# board.net
KiCad netlist of a schematic drawn in EAGLE
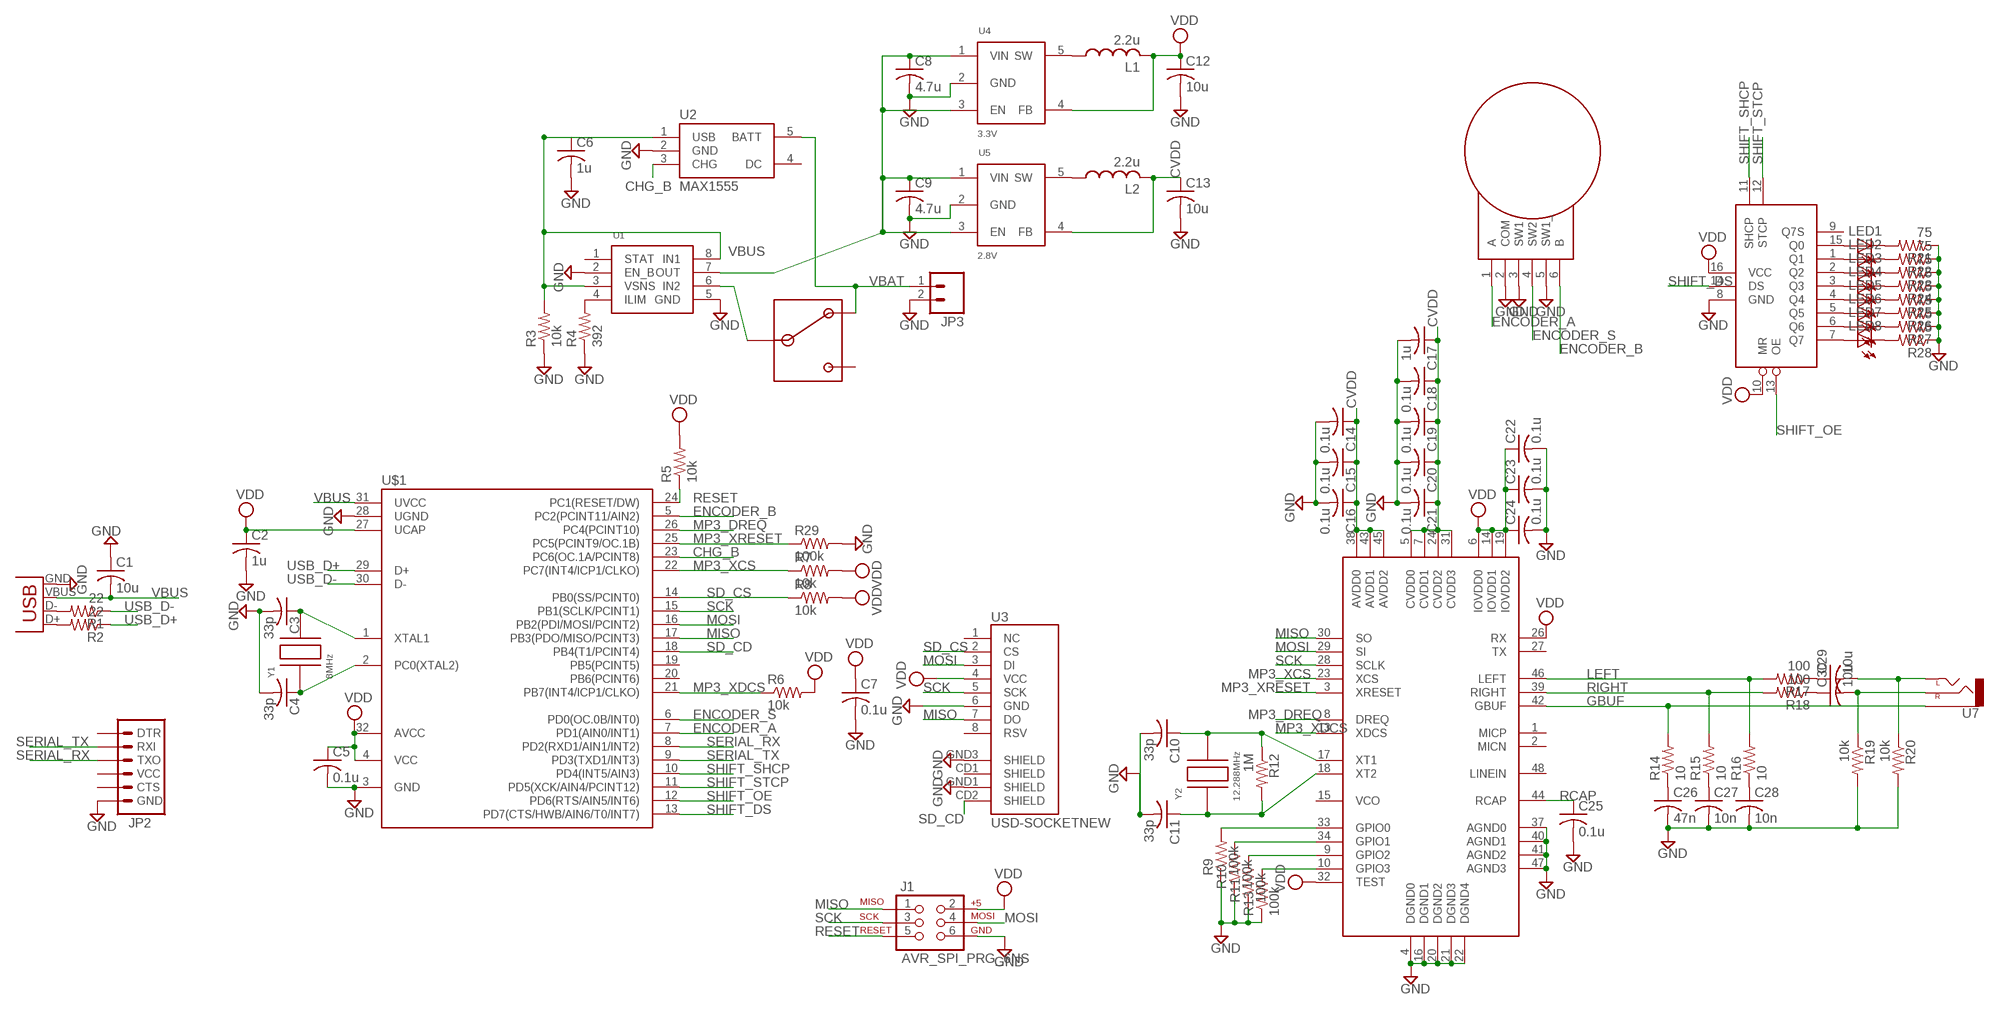
[diagram p0: schematic, sheet 1]

(export (version "E")
  (design (tool "Eeschema 10.0.6"))
  (components
    (comp (ref "C1")
      (value "10u")
      (footprint "eagle-import:C0603K")
      (libsource (lib "eagle-import") (part "C-USC0603K"))
    )
    (comp (ref "C2")
      (value "1u")
      (footprint "eagle-import:C0603K")
      (libsource (lib "eagle-import") (part "C-USC0603K"))
    )
    (comp (ref "C3")
      (value "33p")
      (footprint "eagle-import:C0603K")
      (libsource (lib "eagle-import") (part "C-USC0603K"))
    )
    (comp (ref "C4")
      (value "33p")
      (footprint "eagle-import:C0603K")
      (libsource (lib "eagle-import") (part "C-USC0603K"))
    )
    (comp (ref "C5")
      (value "0.1u")
      (footprint "eagle-import:C0603K")
      (libsource (lib "eagle-import") (part "C-USC0603K"))
    )
    (comp (ref "C6")
      (value "1u")
      (footprint "eagle-import:C0603K")
      (libsource (lib "eagle-import") (part "C-USC0603K"))
    )
    (comp (ref "C7")
      (value "0.1u")
      (footprint "eagle-import:C0603K")
      (libsource (lib "eagle-import") (part "C-USC0603K"))
    )
    (comp (ref "C8")
      (value "4.7u")
      (footprint "eagle-import:C0603K")
      (libsource (lib "eagle-import") (part "C-USC0603K"))
    )
    (comp (ref "C9")
      (value "4.7u")
      (footprint "eagle-import:C0603K")
      (libsource (lib "eagle-import") (part "C-USC0603K"))
    )
    (comp (ref "C10")
      (value "33p")
      (footprint "eagle-import:C0603K")
      (libsource (lib "eagle-import") (part "C-USC0603K"))
    )
    (comp (ref "C11")
      (value "33p")
      (footprint "eagle-import:C0603K")
      (libsource (lib "eagle-import") (part "C-USC0603K"))
    )
    (comp (ref "C12")
      (value "10u")
      (footprint "eagle-import:C0603K")
      (libsource (lib "eagle-import") (part "C-USC0603K"))
    )
    (comp (ref "C13")
      (value "10u")
      (footprint "eagle-import:C0603K")
      (libsource (lib "eagle-import") (part "C-USC0603K"))
    )
    (comp (ref "C14")
      (value "0.1u")
      (footprint "eagle-import:C0603K")
      (libsource (lib "eagle-import") (part "C-USC0603K"))
    )
    (comp (ref "C15")
      (value "0.1u")
      (footprint "eagle-import:C0603K")
      (libsource (lib "eagle-import") (part "C-USC0603K"))
    )
    (comp (ref "C16")
      (value "0.1u")
      (footprint "eagle-import:C0603K")
      (libsource (lib "eagle-import") (part "C-USC0603K"))
    )
    (comp (ref "C17")
      (value "1u")
      (footprint "eagle-import:C0603K")
      (libsource (lib "eagle-import") (part "C-USC0603K"))
    )
    (comp (ref "C18")
      (value "0.1u")
      (footprint "eagle-import:C0603K")
      (libsource (lib "eagle-import") (part "C-USC0603K"))
    )
    (comp (ref "C19")
      (value "0.1u")
      (footprint "eagle-import:C0603K")
      (libsource (lib "eagle-import") (part "C-USC0603K"))
    )
    (comp (ref "C20")
      (value "0.1u")
      (footprint "eagle-import:C0603K")
      (libsource (lib "eagle-import") (part "C-USC0603K"))
    )
    (comp (ref "C21")
      (value "0.1u")
      (footprint "eagle-import:C0603K")
      (libsource (lib "eagle-import") (part "C-USC0603K"))
    )
    (comp (ref "C22")
      (value "0.1u")
      (footprint "eagle-import:C0603K")
      (libsource (lib "eagle-import") (part "C-USC0603K"))
    )
    (comp (ref "C23")
      (value "0.1u")
      (footprint "eagle-import:C0603K")
      (libsource (lib "eagle-import") (part "C-USC0603K"))
    )
    (comp (ref "C24")
      (value "0.1u")
      (footprint "eagle-import:C0603K")
      (libsource (lib "eagle-import") (part "C-USC0603K"))
    )
    (comp (ref "C25")
      (value "0.1u")
      (footprint "eagle-import:C0603K")
      (libsource (lib "eagle-import") (part "C-USC0603K"))
    )
    (comp (ref "C26")
      (value "47n")
      (footprint "eagle-import:C0603K")
      (libsource (lib "eagle-import") (part "C-USC0603K"))
    )
    (comp (ref "C27")
      (value "10n")
      (footprint "eagle-import:C0603K")
      (libsource (lib "eagle-import") (part "C-USC0603K"))
    )
    (comp (ref "C28")
      (value "10n")
      (footprint "eagle-import:C0603K")
      (libsource (lib "eagle-import") (part "C-USC0603K"))
    )
    (comp (ref "C29")
      (value "10u")
      (footprint "eagle-import:C0603K")
      (libsource (lib "eagle-import") (part "C-USC0603K"))
    )
    (comp (ref "C30")
      (value "10u")
      (footprint "eagle-import:C0603K")
      (libsource (lib "eagle-import") (part "C-USC0603K"))
    )
    (comp (ref "J1")
      (value "AVR_SPI_PRG_6NS")
      (footprint "eagle-import:2X3-NS")
      (libsource (lib "eagle-import") (part "AVR_SPI_PRG_6NS"))
    )
    (comp (ref "JP1")
      (value "USBSMD")
      (footprint "eagle-import:USB-MINIB")
      (libsource (lib "eagle-import") (part "USBSMD"))
    )
    (comp (ref "JP2")
      (value "ARDUINO_SERIAL_PROGRAMLOCK")
      (footprint "eagle-import:1X06_LOCK")
      (libsource (lib "eagle-import") (part "ARDUINO_SERIAL_PROGRAMLOCK"))
    )
    (comp (ref "JP3")
      (value "M02PTH")
      (footprint "eagle-import:1X02")
      (libsource (lib "eagle-import") (part "M02PTH"))
    )
    (comp (ref "L1")
      (value "2.2u")
      (footprint "eagle-import:IHLP-2020CZ-11")
      (libsource (lib "eagle-import") (part "IHLP-2020CZ-11"))
    )
    (comp (ref "L2")
      (value "2.2u")
      (footprint "eagle-import:IHLP-2020CZ-11")
      (libsource (lib "eagle-import") (part "IHLP-2020CZ-11"))
    )
    (comp (ref "LED1")
      (value "LED1206")
      (footprint "eagle-import:LED-1206")
      (libsource (lib "eagle-import") (part "LED1206"))
    )
    (comp (ref "LED2")
      (value "LED1206")
      (footprint "eagle-import:LED-1206")
      (libsource (lib "eagle-import") (part "LED1206"))
    )
    (comp (ref "LED3")
      (value "LED1206")
      (footprint "eagle-import:LED-1206")
      (libsource (lib "eagle-import") (part "LED1206"))
    )
    (comp (ref "LED4")
      (value "LED1206")
      (footprint "eagle-import:LED-1206")
      (libsource (lib "eagle-import") (part "LED1206"))
    )
    (comp (ref "LED5")
      (value "LED1206")
      (footprint "eagle-import:LED-1206")
      (libsource (lib "eagle-import") (part "LED1206"))
    )
    (comp (ref "LED6")
      (value "LED1206")
      (footprint "eagle-import:LED-1206")
      (libsource (lib "eagle-import") (part "LED1206"))
    )
    (comp (ref "LED7")
      (value "LED1206")
      (footprint "eagle-import:LED-1206")
      (libsource (lib "eagle-import") (part "LED1206"))
    )
    (comp (ref "LED8")
      (value "LED1206")
      (footprint "eagle-import:LED-1206")
      (libsource (lib "eagle-import") (part "LED1206"))
    )
    (comp (ref "R1")
      (value "22")
      (footprint "eagle-import:R0603W")
      (libsource (lib "eagle-import") (part "R-US_R0603W"))
    )
    (comp (ref "R2")
      (value "22")
      (footprint "eagle-import:R0603W")
      (libsource (lib "eagle-import") (part "R-US_R0603W"))
    )
    (comp (ref "R3")
      (value "10k")
      (footprint "eagle-import:R0603")
      (libsource (lib "eagle-import") (part "R-US_R0603"))
    )
    (comp (ref "R4")
      (value "392")
      (footprint "eagle-import:R0603")
      (libsource (lib "eagle-import") (part "R-US_R0603"))
    )
    (comp (ref "R5")
      (value "10k")
      (footprint "eagle-import:R0603")
      (libsource (lib "eagle-import") (part "R-US_R0603"))
    )
    (comp (ref "R6")
      (value "10k")
      (footprint "eagle-import:R0603W")
      (libsource (lib "eagle-import") (part "R-US_R0603W"))
    )
    (comp (ref "R7")
      (value "10k")
      (footprint "eagle-import:R0603W")
      (libsource (lib "eagle-import") (part "R-US_R0603W"))
    )
    (comp (ref "R8")
      (value "10k")
      (footprint "eagle-import:R0603W")
      (libsource (lib "eagle-import") (part "R-US_R0603W"))
    )
    (comp (ref "R9")
      (value "100k")
      (footprint "eagle-import:R0603W")
      (libsource (lib "eagle-import") (part "R-US_R0603W"))
    )
    (comp (ref "R10")
      (value "100k")
      (footprint "eagle-import:R0603W")
      (libsource (lib "eagle-import") (part "R-US_R0603W"))
    )
    (comp (ref "R11")
      (value "100k")
      (footprint "eagle-import:R0603W")
      (libsource (lib "eagle-import") (part "R-US_R0603W"))
    )
    (comp (ref "R12")
      (value "1M")
      (footprint "eagle-import:R0603")
      (libsource (lib "eagle-import") (part "R-US_R0603"))
    )
    (comp (ref "R13")
      (value "100k")
      (footprint "eagle-import:R0603W")
      (libsource (lib "eagle-import") (part "R-US_R0603W"))
    )
    (comp (ref "R14")
      (value "10")
      (footprint "eagle-import:R0603W")
      (libsource (lib "eagle-import") (part "R-US_R0603W"))
    )
    (comp (ref "R15")
      (value "10")
      (footprint "eagle-import:R0603W")
      (libsource (lib "eagle-import") (part "R-US_R0603W"))
    )
    (comp (ref "R16")
      (value "10")
      (footprint "eagle-import:R0603W")
      (libsource (lib "eagle-import") (part "R-US_R0603W"))
    )
    (comp (ref "R17")
      (value "100")
      (footprint "eagle-import:R0603W")
      (libsource (lib "eagle-import") (part "R-US_R0603W"))
    )
    (comp (ref "R18")
      (value "100")
      (footprint "eagle-import:R0603W")
      (libsource (lib "eagle-import") (part "R-US_R0603W"))
    )
    (comp (ref "R19")
      (value "10k")
      (footprint "eagle-import:R0603W")
      (libsource (lib "eagle-import") (part "R-US_R0603W"))
    )
    (comp (ref "R20")
      (value "10k")
      (footprint "eagle-import:R0603W")
      (libsource (lib "eagle-import") (part "R-US_R0603W"))
    )
    (comp (ref "R21")
      (value "75")
      (footprint "eagle-import:R0603W")
      (libsource (lib "eagle-import") (part "R-US_R0603W"))
    )
    (comp (ref "R22")
      (value "75")
      (footprint "eagle-import:R0603W")
      (libsource (lib "eagle-import") (part "R-US_R0603W"))
    )
    (comp (ref "R23")
      (value "75")
      (footprint "eagle-import:R0603W")
      (libsource (lib "eagle-import") (part "R-US_R0603W"))
    )
    (comp (ref "R24")
      (value "75")
      (footprint "eagle-import:R0603W")
      (libsource (lib "eagle-import") (part "R-US_R0603W"))
    )
    (comp (ref "R25")
      (value "75")
      (footprint "eagle-import:R0603W")
      (libsource (lib "eagle-import") (part "R-US_R0603W"))
    )
    (comp (ref "R26")
      (value "75")
      (footprint "eagle-import:R0603W")
      (libsource (lib "eagle-import") (part "R-US_R0603W"))
    )
    (comp (ref "R27")
      (value "75")
      (footprint "eagle-import:R0603W")
      (libsource (lib "eagle-import") (part "R-US_R0603W"))
    )
    (comp (ref "R28")
      (value "75")
      (footprint "eagle-import:R0603W")
      (libsource (lib "eagle-import") (part "R-US_R0603W"))
    )
    (comp (ref "R29")
      (value "100k")
      (footprint "eagle-import:R0603W")
      (libsource (lib "eagle-import") (part "R-US_R0603W"))
    )
    (comp (ref "S1")
      (value "JS102011SAQN")
      (footprint "eagle-import:JS102011SAQN")
      (libsource (lib "eagle-import") (part "JS102011SAQN"))
    )
    (comp (ref "S2")
      (value "EVQ-WKA")
      (footprint "eagle-import:EVQ-WKA")
      (libsource (lib "eagle-import") (part "EVQ-WKA"))
    )
    (comp (ref "U$1")
      (value "ATMEGA32U2")
      (footprint "eagle-import:TQFP32-08")
      (libsource (lib "eagle-import") (part "ATMEGA32U2"))
    )
    (comp (ref "U$2")
      (value "VS1003")
      (footprint "eagle-import:LQFP-48")
      (libsource (lib "eagle-import") (part "VS1003"))
    )
    (comp (ref "U1")
      (value "TPS2112A")
      (footprint "eagle-import:TSSOP8")
      (libsource (lib "eagle-import") (part "TPS2112A"))
    )
    (comp (ref "U2")
      (value "MAX1555")
      (footprint "eagle-import:SOT23-5")
      (libsource (lib "eagle-import") (part "MAX1555"))
    )
    (comp (ref "U3")
      (value "USD-SOCKETNEW")
      (footprint "eagle-import:MICRO-SD-SOCKET-PP")
      (libsource (lib "eagle-import") (part "USD-SOCKETNEW"))
    )
    (comp (ref "U4")
      (value "3.3V")
      (footprint "eagle-import:SOT23-5")
      (libsource (lib "eagle-import") (part "LM3671"))
    )
    (comp (ref "U5")
      (value "2.8V")
      (footprint "eagle-import:SOT23-5")
      (libsource (lib "eagle-import") (part "LM3671"))
    )
    (comp (ref "U6")
      (value "74HC595")
      (footprint "eagle-import:TSSOP16")
      (libsource (lib "eagle-import") (part "74HC595"))
    )
    (comp (ref "U7")
      (value "AUDIO-JACKSMD2")
      (footprint "eagle-import:AUDIO-JACK-3.5MM-SMD")
      (libsource (lib "eagle-import") (part "AUDIO-JACKSMD2"))
    )
    (comp (ref "Y1")
      (value "8MHz")
      (footprint "eagle-import:HC49_US")
      (libsource (lib "eagle-import") (part "CSM-7X"))
    )
    (comp (ref "Y2")
      (value "12.288MHz")
      (footprint "eagle-import:CSM-3X")
      (libsource (lib "eagle-import") (part "CSM-3X"))
    )
  )
  (nets
    (net (code "1") (name "/CHG_B") (class "Default")
      (node (ref "U$1") (pin "23") (pinfunction "PC6(OC.1A/PCINT8)_23") (pintype "bidirectional"))
      (node (ref "U2") (pin "3") (pinfunction "CHG_3") (pintype "bidirectional"))
    )
    (net (code "2") (name "/CVDD") (class "Default")
      (node (ref "C13") (pin "1") (pinfunction "1_1") (pintype "passive"))
      (node (ref "C14") (pin "1") (pinfunction "1_1") (pintype "passive"))
      (node (ref "C15") (pin "1") (pinfunction "1_1") (pintype "passive"))
      (node (ref "C16") (pin "1") (pinfunction "1_1") (pintype "passive"))
      (node (ref "C17") (pin "1") (pinfunction "1_1") (pintype "passive"))
      (node (ref "C18") (pin "1") (pinfunction "1_1") (pintype "passive"))
      (node (ref "C19") (pin "1") (pinfunction "1_1") (pintype "passive"))
      (node (ref "C20") (pin "1") (pinfunction "1_1") (pintype "passive"))
      (node (ref "C21") (pin "1") (pinfunction "1_1") (pintype "passive"))
      (node (ref "L2") (pin "P$2") (pinfunction "2_P$2") (pintype "passive"))
      (node (ref "U$2") (pin "24") (pinfunction "CVDD2_24") (pintype "bidirectional"))
      (node (ref "U$2") (pin "31") (pinfunction "CVDD3_31") (pintype "bidirectional"))
      (node (ref "U$2") (pin "38") (pinfunction "AVDD0_38") (pintype "bidirectional"))
      (node (ref "U$2") (pin "43") (pinfunction "AVDD1_43") (pintype "bidirectional"))
      (node (ref "U$2") (pin "45") (pinfunction "AVDD2_45") (pintype "bidirectional"))
      (node (ref "U$2") (pin "5") (pinfunction "CVDD0_5") (pintype "bidirectional"))
      (node (ref "U$2") (pin "7") (pinfunction "CVDD1_7") (pintype "bidirectional"))
      (node (ref "U5") (pin "4") (pinfunction "FB_4") (pintype "bidirectional"))
    )
    (net (code "3") (name "/ENCODER_A") (class "Default")
      (node (ref "S2") (pin "1") (pinfunction "A_1") (pintype "bidirectional"))
      (node (ref "U$1") (pin "7") (pinfunction "PD1(AIN0/INT1)_7") (pintype "bidirectional"))
    )
    (net (code "4") (name "/ENCODER_B") (class "Default")
      (node (ref "S2") (pin "6") (pinfunction "B_6") (pintype "bidirectional"))
      (node (ref "U$1") (pin "5") (pinfunction "PC2(PCINT11/AIN2)_5") (pintype "bidirectional"))
    )
    (net (code "5") (name "/ENCODER_S") (class "Default")
      (node (ref "S2") (pin "4") (pinfunction "SW2_4") (pintype "bidirectional"))
      (node (ref "U$1") (pin "6") (pinfunction "PD0(OC.0B/INT0)_6") (pintype "bidirectional"))
    )
    (net (code "6") (name "/GBUF") (class "Default")
      (node (ref "R14") (pin "2") (pinfunction "2_2") (pintype "passive"))
      (node (ref "U$2") (pin "42") (pinfunction "GBUF_42") (pintype "bidirectional"))
      (node (ref "U7") (pin "SLEEVE") (pinfunction "SLEEVE_SLEEVE") (pintype "bidirectional"))
    )
    (net (code "7") (name "/LEFT") (class "Default")
      (node (ref "R16") (pin "2") (pinfunction "2_2") (pintype "passive"))
      (node (ref "R17") (pin "2") (pinfunction "2_2") (pintype "passive"))
      (node (ref "U$2") (pin "46") (pinfunction "LEFT_46") (pintype "bidirectional"))
    )
    (net (code "8") (name "/MISO") (class "Default")
      (node (ref "J1") (pin "1") (pinfunction "1_1") (pintype "passive"))
      (node (ref "U$1") (pin "17") (pinfunction "PB3(PDO/MISO/PCINT3)_17") (pintype "bidirectional"))
      (node (ref "U$2") (pin "30") (pinfunction "SO_30") (pintype "bidirectional"))
      (node (ref "U3") (pin "7") (pinfunction "DO_7") (pintype "bidirectional"))
    )
    (net (code "9") (name "/MOSI") (class "Default")
      (node (ref "J1") (pin "4") (pinfunction "4_4") (pintype "passive"))
      (node (ref "U$1") (pin "16") (pinfunction "PB2(PDI/MOSI/PCINT2)_16") (pintype "bidirectional"))
      (node (ref "U$2") (pin "29") (pinfunction "SI_29") (pintype "bidirectional"))
      (node (ref "U3") (pin "3") (pinfunction "DI_3") (pintype "bidirectional"))
    )
    (net (code "10") (name "/MP3_DREQ") (class "Default")
      (node (ref "U$1") (pin "26") (pinfunction "PC4(PCINT10)_26") (pintype "bidirectional"))
      (node (ref "U$2") (pin "8") (pinfunction "DREQ_8") (pintype "bidirectional"))
    )
    (net (code "11") (name "/MP3_XCS") (class "Default")
      (node (ref "R7") (pin "1") (pinfunction "1_1") (pintype "passive"))
      (node (ref "U$1") (pin "22") (pinfunction "PC7(INT4/ICP1/CLKO)_22") (pintype "bidirectional"))
      (node (ref "U$2") (pin "23") (pinfunction "XCS_23") (pintype "bidirectional"))
    )
    (net (code "12") (name "/MP3_XDCS") (class "Default")
      (node (ref "R6") (pin "1") (pinfunction "1_1") (pintype "passive"))
      (node (ref "U$1") (pin "21") (pinfunction "PB7(INT4/ICP1/CLKO)_21") (pintype "bidirectional"))
      (node (ref "U$2") (pin "13") (pinfunction "XDCS_13") (pintype "bidirectional"))
    )
    (net (code "13") (name "/MP3_XRESET") (class "Default")
      (node (ref "R29") (pin "1") (pinfunction "1_1") (pintype "passive"))
      (node (ref "U$1") (pin "25") (pinfunction "PC5(PCINT9/OC.1B)_25") (pintype "bidirectional"))
      (node (ref "U$2") (pin "3") (pinfunction "XRESET_3") (pintype "bidirectional"))
    )
    (net (code "14") (name "/RCAP") (class "Default")
      (node (ref "C25") (pin "1") (pinfunction "1_1") (pintype "passive"))
      (node (ref "U$2") (pin "44") (pinfunction "RCAP_44") (pintype "bidirectional"))
    )
    (net (code "15") (name "/RESET") (class "Default")
      (node (ref "J1") (pin "5") (pinfunction "5_5") (pintype "passive"))
      (node (ref "R5") (pin "1") (pinfunction "1_1") (pintype "passive"))
      (node (ref "U$1") (pin "24") (pinfunction "PC1(RESET/DW)_24") (pintype "bidirectional"))
    )
    (net (code "16") (name "/RIGHT") (class "Default")
      (node (ref "R15") (pin "2") (pinfunction "2_2") (pintype "passive"))
      (node (ref "R18") (pin "2") (pinfunction "2_2") (pintype "passive"))
      (node (ref "U$2") (pin "39") (pinfunction "RIGHT_39") (pintype "bidirectional"))
    )
    (net (code "17") (name "/SCK") (class "Default")
      (node (ref "J1") (pin "3") (pinfunction "3_3") (pintype "passive"))
      (node (ref "U$1") (pin "15") (pinfunction "PB1(SCLK/PCINT1)_15") (pintype "bidirectional"))
      (node (ref "U$2") (pin "28") (pinfunction "SCLK_28") (pintype "bidirectional"))
      (node (ref "U3") (pin "5") (pinfunction "SCK_5") (pintype "bidirectional"))
    )
    (net (code "18") (name "/SD_CD") (class "Default")
      (node (ref "U$1") (pin "18") (pinfunction "PB4(T1/PCINT4)_18") (pintype "bidirectional"))
      (node (ref "U3") (pin "CD2") (pinfunction "SHIELD_CD2") (pintype "bidirectional"))
    )
    (net (code "19") (name "/SD_CS") (class "Default")
      (node (ref "R8") (pin "1") (pinfunction "1_1") (pintype "passive"))
      (node (ref "U$1") (pin "14") (pinfunction "PB0(SS/PCINT0)_14") (pintype "bidirectional"))
      (node (ref "U3") (pin "2") (pinfunction "CS_2") (pintype "bidirectional"))
    )
    (net (code "20") (name "/SERIAL_RX") (class "Default")
      (node (ref "JP2") (pin "3") (pinfunction "TXO_3") (pintype "passive"))
      (node (ref "U$1") (pin "8") (pinfunction "PD2(RXD1/AIN1/INT2)_8") (pintype "bidirectional"))
    )
    (net (code "21") (name "/SERIAL_TX") (class "Default")
      (node (ref "JP2") (pin "2") (pinfunction "RXI_2") (pintype "passive"))
      (node (ref "U$1") (pin "9") (pinfunction "PD3(TXD1/INT3)_9") (pintype "bidirectional"))
    )
    (net (code "22") (name "/SHIFT_DS") (class "Default")
      (node (ref "U$1") (pin "13") (pinfunction "PD7(CTS/HWB/AIN6/T0/INT7)_13") (pintype "bidirectional"))
      (node (ref "U6") (pin "14") (pinfunction "DS_14") (pintype "bidirectional"))
    )
    (net (code "23") (name "/SHIFT_OE") (class "Default")
      (node (ref "U$1") (pin "12") (pinfunction "PD6(RTS/AIN5/INT6)_12") (pintype "bidirectional"))
      (node (ref "U6") (pin "13") (pinfunction "OE_13") (pintype "bidirectional"))
    )
    (net (code "24") (name "/SHIFT_SHCP") (class "Default")
      (node (ref "U$1") (pin "10") (pinfunction "PD4(INT5/AIN3)_10") (pintype "bidirectional"))
      (node (ref "U6") (pin "11") (pinfunction "SHCP_11") (pintype "bidirectional"))
    )
    (net (code "25") (name "/SHIFT_STCP") (class "Default")
      (node (ref "U$1") (pin "11") (pinfunction "PD5(XCK/AIN4/PCINT12)_11") (pintype "bidirectional"))
      (node (ref "U6") (pin "12") (pinfunction "STCP_12") (pintype "bidirectional"))
    )
    (net (code "26") (name "/USB_D+") (class "Default")
      (node (ref "R2") (pin "1") (pinfunction "1_1") (pintype "passive"))
      (node (ref "U$1") (pin "29") (pinfunction "D+_29") (pintype "passive"))
    )
    (net (code "27") (name "/USB_D-") (class "Default")
      (node (ref "R1") (pin "1") (pinfunction "1_1") (pintype "passive"))
      (node (ref "U$1") (pin "30") (pinfunction "D-_30") (pintype "passive"))
    )
    (net (code "28") (name "/VBAT") (class "Default")
      (node (ref "JP3") (pin "1") (pinfunction "1_1") (pintype "passive"))
      (node (ref "S1") (pin "P$3") (pinfunction "3_P$3") (pintype "bidirectional"))
      (node (ref "U2") (pin "5") (pinfunction "BATT_5") (pintype "bidirectional"))
    )
    (net (code "29") (name "/VBUS") (class "Default")
      (node (ref "C1") (pin "2") (pinfunction "2_2") (pintype "passive"))
      (node (ref "C6") (pin "1") (pinfunction "1_1") (pintype "passive"))
      (node (ref "JP1") (pin "VBUS") (pinfunction "VBUS_VBUS") (pintype "bidirectional"))
      (node (ref "R3") (pin "2") (pinfunction "2_2") (pintype "passive"))
      (node (ref "U$1") (pin "31") (pinfunction "UVCC_31") (pintype "passive"))
      (node (ref "U1") (pin "3") (pinfunction "VSNS_3") (pintype "bidirectional"))
      (node (ref "U1") (pin "8") (pinfunction "IN1_8") (pintype "bidirectional"))
      (node (ref "U2") (pin "1") (pinfunction "USB_1") (pintype "bidirectional"))
    )
    (net (code "30") (name "GND") (class "Default")
      (node (ref "C1") (pin "1") (pinfunction "1_1") (pintype "passive"))
      (node (ref "C10") (pin "2") (pinfunction "2_2") (pintype "passive"))
      (node (ref "C11") (pin "2") (pinfunction "2_2") (pintype "passive"))
      (node (ref "C12") (pin "2") (pinfunction "2_2") (pintype "passive"))
      (node (ref "C13") (pin "2") (pinfunction "2_2") (pintype "passive"))
      (node (ref "C14") (pin "2") (pinfunction "2_2") (pintype "passive"))
      (node (ref "C15") (pin "2") (pinfunction "2_2") (pintype "passive"))
      (node (ref "C16") (pin "2") (pinfunction "2_2") (pintype "passive"))
      (node (ref "C17") (pin "2") (pinfunction "2_2") (pintype "passive"))
      (node (ref "C18") (pin "2") (pinfunction "2_2") (pintype "passive"))
      (node (ref "C19") (pin "2") (pinfunction "2_2") (pintype "passive"))
      (node (ref "C2") (pin "2") (pinfunction "2_2") (pintype "passive"))
      (node (ref "C20") (pin "2") (pinfunction "2_2") (pintype "passive"))
      (node (ref "C21") (pin "2") (pinfunction "2_2") (pintype "passive"))
      (node (ref "C22") (pin "2") (pinfunction "2_2") (pintype "passive"))
      (node (ref "C23") (pin "2") (pinfunction "2_2") (pintype "passive"))
      (node (ref "C24") (pin "2") (pinfunction "2_2") (pintype "passive"))
      (node (ref "C25") (pin "2") (pinfunction "2_2") (pintype "passive"))
      (node (ref "C26") (pin "2") (pinfunction "2_2") (pintype "passive"))
      (node (ref "C27") (pin "2") (pinfunction "2_2") (pintype "passive"))
      (node (ref "C28") (pin "2") (pinfunction "2_2") (pintype "passive"))
      (node (ref "C3") (pin "2") (pinfunction "2_2") (pintype "passive"))
      (node (ref "C4") (pin "2") (pinfunction "2_2") (pintype "passive"))
      (node (ref "C5") (pin "2") (pinfunction "2_2") (pintype "passive"))
      (node (ref "C6") (pin "2") (pinfunction "2_2") (pintype "passive"))
      (node (ref "C7") (pin "2") (pinfunction "2_2") (pintype "passive"))
      (node (ref "C8") (pin "2") (pinfunction "2_2") (pintype "passive"))
      (node (ref "C9") (pin "2") (pinfunction "2_2") (pintype "passive"))
      (node (ref "J1") (pin "6") (pinfunction "6_6") (pintype "passive"))
      (node (ref "JP1") (pin "GND") (pinfunction "GND_GND") (pintype "bidirectional"))
      (node (ref "JP2") (pin "6") (pinfunction "GND_6") (pintype "passive"))
      (node (ref "JP3") (pin "2") (pinfunction "2_2") (pintype "passive"))
      (node (ref "R10") (pin "1") (pinfunction "1_1") (pintype "passive"))
      (node (ref "R11") (pin "1") (pinfunction "1_1") (pintype "passive"))
      (node (ref "R13") (pin "1") (pinfunction "1_1") (pintype "passive"))
      (node (ref "R19") (pin "2") (pinfunction "2_2") (pintype "passive"))
      (node (ref "R20") (pin "2") (pinfunction "2_2") (pintype "passive"))
      (node (ref "R21") (pin "1") (pinfunction "1_1") (pintype "passive"))
      (node (ref "R22") (pin "1") (pinfunction "1_1") (pintype "passive"))
      (node (ref "R23") (pin "1") (pinfunction "1_1") (pintype "passive"))
      (node (ref "R24") (pin "1") (pinfunction "1_1") (pintype "passive"))
      (node (ref "R25") (pin "1") (pinfunction "1_1") (pintype "passive"))
      (node (ref "R26") (pin "1") (pinfunction "1_1") (pintype "passive"))
      (node (ref "R27") (pin "1") (pinfunction "1_1") (pintype "passive"))
      (node (ref "R28") (pin "1") (pinfunction "1_1") (pintype "passive"))
      (node (ref "R29") (pin "2") (pinfunction "2_2") (pintype "passive"))
      (node (ref "R3") (pin "1") (pinfunction "1_1") (pintype "passive"))
      (node (ref "R4") (pin "1") (pinfunction "1_1") (pintype "passive"))
      (node (ref "R9") (pin "1") (pinfunction "1_1") (pintype "passive"))
      (node (ref "S2") (pin "2") (pinfunction "COM_2") (pintype "bidirectional"))
      (node (ref "S2") (pin "3") (pinfunction "SW1_3") (pintype "bidirectional"))
      (node (ref "S2") (pin "5") (pinfunction "SW1__5") (pintype "bidirectional"))
      (node (ref "U$1") (pin "28") (pinfunction "UGND_28") (pintype "passive"))
      (node (ref "U$1") (pin "3") (pinfunction "GND_3") (pintype "power_in"))
      (node (ref "U$2") (pin "16") (pinfunction "DGND1_16") (pintype "bidirectional"))
      (node (ref "U$2") (pin "20") (pinfunction "DGND2_20") (pintype "bidirectional"))
      (node (ref "U$2") (pin "21") (pinfunction "DGND3_21") (pintype "bidirectional"))
      (node (ref "U$2") (pin "22") (pinfunction "DGND4_22") (pintype "bidirectional"))
      (node (ref "U$2") (pin "37") (pinfunction "AGND0_37") (pintype "bidirectional"))
      (node (ref "U$2") (pin "4") (pinfunction "DGND0_4") (pintype "bidirectional"))
      (node (ref "U$2") (pin "40") (pinfunction "AGND1_40") (pintype "bidirectional"))
      (node (ref "U$2") (pin "41") (pinfunction "AGND2_41") (pintype "bidirectional"))
      (node (ref "U$2") (pin "47") (pinfunction "AGND3_47") (pintype "bidirectional"))
      (node (ref "U1") (pin "2") (pinfunction "EN_B_2") (pintype "bidirectional"))
      (node (ref "U1") (pin "5") (pinfunction "GND_5") (pintype "bidirectional"))
      (node (ref "U2") (pin "2") (pinfunction "GND_2") (pintype "bidirectional"))
      (node (ref "U3") (pin "6") (pinfunction "GND_6") (pintype "bidirectional"))
      (node (ref "U3") (pin "GND1") (pinfunction "SHIELD_GND1") (pintype "bidirectional"))
      (node (ref "U3") (pin "GND3") (pinfunction "SHIELD_GND3") (pintype "bidirectional"))
      (node (ref "U4") (pin "2") (pinfunction "GND_2") (pintype "bidirectional"))
      (node (ref "U5") (pin "2") (pinfunction "GND_2") (pintype "bidirectional"))
      (node (ref "U6") (pin "8") (pinfunction "GND_8") (pintype "bidirectional"))
    )
    (net (code "31") (name "Net-(C26-Pad1)") (class "Default")
      (node (ref "C26") (pin "1") (pinfunction "1_1") (pintype "passive"))
      (node (ref "R14") (pin "1") (pinfunction "1_1") (pintype "passive"))
    )
    (net (code "32") (name "Net-(C27-Pad1)") (class "Default")
      (node (ref "C27") (pin "1") (pinfunction "1_1") (pintype "passive"))
      (node (ref "R15") (pin "1") (pinfunction "1_1") (pintype "passive"))
    )
    (net (code "33") (name "Net-(C28-Pad1)") (class "Default")
      (node (ref "C28") (pin "1") (pinfunction "1_1") (pintype "passive"))
      (node (ref "R16") (pin "1") (pinfunction "1_1") (pintype "passive"))
    )
    (net (code "34") (name "Net-(C29-Pad1)") (class "Default")
      (node (ref "C29") (pin "1") (pinfunction "1_1") (pintype "passive"))
      (node (ref "R17") (pin "1") (pinfunction "1_1") (pintype "passive"))
    )
    (net (code "35") (name "Net-(C30-Pad1)") (class "Default")
      (node (ref "C30") (pin "1") (pinfunction "1_1") (pintype "passive"))
      (node (ref "R18") (pin "1") (pinfunction "1_1") (pintype "passive"))
    )
    (net (code "36") (name "Net-(JP1-PadD+)") (class "Default")
      (node (ref "JP1") (pin "D+") (pinfunction "D+_D+") (pintype "bidirectional"))
      (node (ref "R2") (pin "2") (pinfunction "2_2") (pintype "passive"))
    )
    (net (code "37") (name "Net-(JP1-PadD-)") (class "Default")
      (node (ref "JP1") (pin "D-") (pinfunction "D-_D-") (pintype "bidirectional"))
      (node (ref "R1") (pin "2") (pinfunction "2_2") (pintype "passive"))
    )
    (net (code "38") (name "Net-(L1-1)") (class "Default")
      (node (ref "L1") (pin "P$1") (pinfunction "1_P$1") (pintype "passive"))
      (node (ref "U4") (pin "5") (pinfunction "SW_5") (pintype "bidirectional"))
    )
    (net (code "39") (name "Net-(L2-1)") (class "Default")
      (node (ref "L2") (pin "P$1") (pinfunction "1_P$1") (pintype "passive"))
      (node (ref "U5") (pin "5") (pinfunction "SW_5") (pintype "bidirectional"))
    )
    (net (code "40") (name "Net-(LED1-PadC)") (class "Default")
      (node (ref "LED1") (pin "C") (pinfunction "C_C") (pintype "passive"))
      (node (ref "R21") (pin "2") (pinfunction "2_2") (pintype "passive"))
    )
    (net (code "41") (name "Net-(LED2-PadC)") (class "Default")
      (node (ref "LED2") (pin "C") (pinfunction "C_C") (pintype "passive"))
      (node (ref "R22") (pin "2") (pinfunction "2_2") (pintype "passive"))
    )
    (net (code "42") (name "Net-(LED3-PadC)") (class "Default")
      (node (ref "LED3") (pin "C") (pinfunction "C_C") (pintype "passive"))
      (node (ref "R23") (pin "2") (pinfunction "2_2") (pintype "passive"))
    )
    (net (code "43") (name "Net-(LED4-PadC)") (class "Default")
      (node (ref "LED4") (pin "C") (pinfunction "C_C") (pintype "passive"))
      (node (ref "R24") (pin "2") (pinfunction "2_2") (pintype "passive"))
    )
    (net (code "44") (name "Net-(LED5-PadC)") (class "Default")
      (node (ref "LED5") (pin "C") (pinfunction "C_C") (pintype "passive"))
      (node (ref "R25") (pin "2") (pinfunction "2_2") (pintype "passive"))
    )
    (net (code "45") (name "Net-(LED6-PadC)") (class "Default")
      (node (ref "LED6") (pin "C") (pinfunction "C_C") (pintype "passive"))
      (node (ref "R26") (pin "2") (pinfunction "2_2") (pintype "passive"))
    )
    (net (code "46") (name "Net-(LED7-PadC)") (class "Default")
      (node (ref "LED7") (pin "C") (pinfunction "C_C") (pintype "passive"))
      (node (ref "R27") (pin "2") (pinfunction "2_2") (pintype "passive"))
    )
    (net (code "47") (name "Net-(LED8-PadC)") (class "Default")
      (node (ref "LED8") (pin "C") (pinfunction "C_C") (pintype "passive"))
      (node (ref "R28") (pin "2") (pinfunction "2_2") (pintype "passive"))
    )
    (net (code "48") (name "Net-(S1-2)") (class "Default")
      (node (ref "S1") (pin "P$2") (pinfunction "2_P$2") (pintype "bidirectional"))
      (node (ref "U1") (pin "6") (pinfunction "IN2_6") (pintype "bidirectional"))
    )
    (net (code "49") (name "Net-(U$1-PC0(XTAL2))") (class "Default")
      (node (ref "C4") (pin "1") (pinfunction "1_1") (pintype "passive"))
      (node (ref "U$1") (pin "2") (pinfunction "PC0(XTAL2)_2") (pintype "bidirectional"))
      (node (ref "Y1") (pin "P$1") (pinfunction "P$1_P$1") (pintype "bidirectional"))
    )
    (net (code "50") (name "Net-(U$1-XTAL1)") (class "Default")
      (node (ref "C3") (pin "1") (pinfunction "1_1") (pintype "passive"))
      (node (ref "U$1") (pin "1") (pinfunction "XTAL1_1") (pintype "bidirectional"))
      (node (ref "Y1") (pin "P$2") (pinfunction "P$2_P$2") (pintype "bidirectional"))
    )
    (net (code "51") (name "Net-(U$2-GPIO0)") (class "Default")
      (node (ref "R9") (pin "2") (pinfunction "2_2") (pintype "passive"))
      (node (ref "U$2") (pin "33") (pinfunction "GPIO0_33") (pintype "bidirectional"))
    )
    (net (code "52") (name "Net-(U$2-GPIO1)") (class "Default")
      (node (ref "R10") (pin "2") (pinfunction "2_2") (pintype "passive"))
      (node (ref "U$2") (pin "34") (pinfunction "GPIO1_34") (pintype "bidirectional"))
    )
    (net (code "53") (name "Net-(U$2-GPIO2)") (class "Default")
      (node (ref "R11") (pin "2") (pinfunction "2_2") (pintype "passive"))
      (node (ref "U$2") (pin "9") (pinfunction "GPIO2_9") (pintype "bidirectional"))
    )
    (net (code "54") (name "Net-(U$2-GPIO3)") (class "Default")
      (node (ref "R13") (pin "2") (pinfunction "2_2") (pintype "passive"))
      (node (ref "U$2") (pin "10") (pinfunction "GPIO3_10") (pintype "bidirectional"))
    )
    (net (code "55") (name "Net-(U$2-XT1)") (class "Default")
      (node (ref "C10") (pin "1") (pinfunction "1_1") (pintype "passive"))
      (node (ref "R12") (pin "1") (pinfunction "1_1") (pintype "passive"))
      (node (ref "U$2") (pin "17") (pinfunction "XT1_17") (pintype "bidirectional"))
      (node (ref "Y2") (pin "P$2") (pinfunction "P$2_P$2") (pintype "bidirectional"))
    )
    (net (code "56") (name "Net-(U$2-XT2)") (class "Default")
      (node (ref "C11") (pin "1") (pinfunction "1_1") (pintype "passive"))
      (node (ref "R12") (pin "2") (pinfunction "2_2") (pintype "passive"))
      (node (ref "U$2") (pin "18") (pinfunction "XT2_18") (pintype "bidirectional"))
      (node (ref "Y2") (pin "P$1") (pinfunction "P$1_P$1") (pintype "bidirectional"))
    )
    (net (code "57") (name "Net-(U1-ILIM)") (class "Default")
      (node (ref "R4") (pin "2") (pinfunction "2_2") (pintype "passive"))
      (node (ref "U1") (pin "4") (pinfunction "ILIM_4") (pintype "bidirectional"))
    )
    (net (code "58") (name "Net-(U1-OUT)") (class "Default")
      (node (ref "C8") (pin "1") (pinfunction "1_1") (pintype "passive"))
      (node (ref "C9") (pin "1") (pinfunction "1_1") (pintype "passive"))
      (node (ref "U1") (pin "7") (pinfunction "OUT_7") (pintype "bidirectional"))
      (node (ref "U4") (pin "1") (pinfunction "VIN_1") (pintype "bidirectional"))
      (node (ref "U4") (pin "3") (pinfunction "EN_3") (pintype "bidirectional"))
      (node (ref "U5") (pin "1") (pinfunction "VIN_1") (pintype "bidirectional"))
      (node (ref "U5") (pin "3") (pinfunction "EN_3") (pintype "bidirectional"))
    )
    (net (code "59") (name "Net-(U6-Q0)") (class "Default")
      (node (ref "LED1") (pin "A") (pinfunction "A_A") (pintype "passive"))
      (node (ref "U6") (pin "15") (pinfunction "Q0_15") (pintype "bidirectional"))
    )
    (net (code "60") (name "Net-(U6-Q1)") (class "Default")
      (node (ref "LED2") (pin "A") (pinfunction "A_A") (pintype "passive"))
      (node (ref "U6") (pin "1") (pinfunction "Q1_1") (pintype "bidirectional"))
    )
    (net (code "61") (name "Net-(U6-Q2)") (class "Default")
      (node (ref "LED3") (pin "A") (pinfunction "A_A") (pintype "passive"))
      (node (ref "U6") (pin "2") (pinfunction "Q2_2") (pintype "bidirectional"))
    )
    (net (code "62") (name "Net-(U6-Q3)") (class "Default")
      (node (ref "LED4") (pin "A") (pinfunction "A_A") (pintype "passive"))
      (node (ref "U6") (pin "3") (pinfunction "Q3_3") (pintype "bidirectional"))
    )
    (net (code "63") (name "Net-(U6-Q4)") (class "Default")
      (node (ref "LED5") (pin "A") (pinfunction "A_A") (pintype "passive"))
      (node (ref "U6") (pin "4") (pinfunction "Q4_4") (pintype "bidirectional"))
    )
    (net (code "64") (name "Net-(U6-Q5)") (class "Default")
      (node (ref "LED6") (pin "A") (pinfunction "A_A") (pintype "passive"))
      (node (ref "U6") (pin "5") (pinfunction "Q5_5") (pintype "bidirectional"))
    )
    (net (code "65") (name "Net-(U6-Q6)") (class "Default")
      (node (ref "LED7") (pin "A") (pinfunction "A_A") (pintype "passive"))
      (node (ref "U6") (pin "6") (pinfunction "Q6_6") (pintype "bidirectional"))
    )
    (net (code "66") (name "Net-(U6-Q7)") (class "Default")
      (node (ref "LED8") (pin "A") (pinfunction "A_A") (pintype "passive"))
      (node (ref "U6") (pin "7") (pinfunction "Q7_7") (pintype "bidirectional"))
    )
    (net (code "67") (name "Net-(U7-LEFT)") (class "Default")
      (node (ref "C29") (pin "2") (pinfunction "2_2") (pintype "passive"))
      (node (ref "R20") (pin "1") (pinfunction "1_1") (pintype "passive"))
      (node (ref "U7") (pin "TIP") (pinfunction "LEFT_TIP") (pintype "bidirectional"))
    )
    (net (code "68") (name "Net-(U7-RIGHT)") (class "Default")
      (node (ref "C30") (pin "2") (pinfunction "2_2") (pintype "passive"))
      (node (ref "R19") (pin "1") (pinfunction "1_1") (pintype "passive"))
      (node (ref "U7") (pin "RING") (pinfunction "RIGHT_RING") (pintype "bidirectional"))
    )
    (net (code "69") (name "VDD") (class "Default")
      (node (ref "C12") (pin "1") (pinfunction "1_1") (pintype "passive"))
      (node (ref "C2") (pin "1") (pinfunction "1_1") (pintype "passive"))
      (node (ref "C22") (pin "1") (pinfunction "1_1") (pintype "passive"))
      (node (ref "C23") (pin "1") (pinfunction "1_1") (pintype "passive"))
      (node (ref "C24") (pin "1") (pinfunction "1_1") (pintype "passive"))
      (node (ref "C5") (pin "1") (pinfunction "1_1") (pintype "passive"))
      (node (ref "C7") (pin "1") (pinfunction "1_1") (pintype "passive"))
      (node (ref "J1") (pin "2") (pinfunction "2_2") (pintype "passive"))
      (node (ref "L1") (pin "P$2") (pinfunction "2_P$2") (pintype "passive"))
      (node (ref "R5") (pin "2") (pinfunction "2_2") (pintype "passive"))
      (node (ref "R6") (pin "2") (pinfunction "2_2") (pintype "passive"))
      (node (ref "R7") (pin "2") (pinfunction "2_2") (pintype "passive"))
      (node (ref "R8") (pin "2") (pinfunction "2_2") (pintype "passive"))
      (node (ref "U$1") (pin "27") (pinfunction "UCAP_27") (pintype "passive"))
      (node (ref "U$1") (pin "32") (pinfunction "AVCC_32") (pintype "passive"))
      (node (ref "U$1") (pin "4") (pinfunction "VCC_4") (pintype "power_in"))
      (node (ref "U$2") (pin "14") (pinfunction "IOVDD1_14") (pintype "bidirectional"))
      (node (ref "U$2") (pin "19") (pinfunction "IOVDD2_19") (pintype "bidirectional"))
      (node (ref "U$2") (pin "26") (pinfunction "RX_26") (pintype "bidirectional"))
      (node (ref "U$2") (pin "32") (pinfunction "TEST_32") (pintype "bidirectional"))
      (node (ref "U$2") (pin "6") (pinfunction "IOVDD0_6") (pintype "bidirectional"))
      (node (ref "U3") (pin "4") (pinfunction "VCC_4") (pintype "bidirectional"))
      (node (ref "U4") (pin "4") (pinfunction "FB_4") (pintype "bidirectional"))
      (node (ref "U6") (pin "10") (pinfunction "MR_10") (pintype "bidirectional"))
      (node (ref "U6") (pin "16") (pinfunction "VCC_16") (pintype "bidirectional"))
    )
    (net (code "70") (name "unconnected-(JP2-CTS-Pad5)") (class "Default")
      (node (ref "JP2") (pin "5") (pinfunction "CTS_5") (pintype "passive"))
    )
    (net (code "71") (name "unconnected-(JP2-DTR-Pad1)") (class "Default")
      (node (ref "JP2") (pin "1") (pinfunction "DTR_1") (pintype "passive"))
    )
    (net (code "72") (name "unconnected-(JP2-VCC-Pad4)") (class "Default")
      (node (ref "JP2") (pin "4") (pinfunction "VCC_4") (pintype "passive"))
    )
    (net (code "73") (name "unconnected-(S1-1-PadP$1)") (class "Default")
      (node (ref "S1") (pin "P$1") (pinfunction "1_P$1") (pintype "bidirectional"))
    )
    (net (code "74") (name "unconnected-(U$1-PB5(PCINT5)-Pad19)") (class "Default")
      (node (ref "U$1") (pin "19") (pinfunction "PB5(PCINT5)_19") (pintype "bidirectional"))
    )
    (net (code "75") (name "unconnected-(U$1-PB6(PCINT6)-Pad20)") (class "Default")
      (node (ref "U$1") (pin "20") (pinfunction "PB6(PCINT6)_20") (pintype "bidirectional"))
    )
    (net (code "76") (name "unconnected-(U$2-LINEIN-Pad48)") (class "Default")
      (node (ref "U$2") (pin "48") (pinfunction "LINEIN_48") (pintype "bidirectional"))
    )
    (net (code "77") (name "unconnected-(U$2-MICN-Pad2)") (class "Default")
      (node (ref "U$2") (pin "2") (pinfunction "MICN_2") (pintype "bidirectional"))
    )
    (net (code "78") (name "unconnected-(U$2-MICP-Pad1)") (class "Default")
      (node (ref "U$2") (pin "1") (pinfunction "MICP_1") (pintype "bidirectional"))
    )
    (net (code "79") (name "unconnected-(U$2-TX-Pad27)") (class "Default")
      (node (ref "U$2") (pin "27") (pinfunction "TX_27") (pintype "bidirectional"))
    )
    (net (code "80") (name "unconnected-(U$2-VCO-Pad15)") (class "Default")
      (node (ref "U$2") (pin "15") (pinfunction "VCO_15") (pintype "bidirectional"))
    )
    (net (code "81") (name "unconnected-(U1-STAT-Pad1)") (class "Default")
      (node (ref "U1") (pin "1") (pinfunction "STAT_1") (pintype "bidirectional"))
    )
    (net (code "82") (name "unconnected-(U2-DC-Pad4)") (class "Default")
      (node (ref "U2") (pin "4") (pinfunction "DC_4") (pintype "bidirectional"))
    )
    (net (code "83") (name "unconnected-(U3-NC-Pad1)") (class "Default")
      (node (ref "U3") (pin "1") (pinfunction "NC_1") (pintype "bidirectional"))
    )
    (net (code "84") (name "unconnected-(U3-RSV-Pad8)") (class "Default")
      (node (ref "U3") (pin "8") (pinfunction "RSV_8") (pintype "bidirectional"))
    )
    (net (code "85") (name "unconnected-(U3-SHIELD-PadCD1)") (class "Default")
      (node (ref "U3") (pin "CD1") (pinfunction "SHIELD_CD1") (pintype "bidirectional"))
    )
    (net (code "86") (name "unconnected-(U6-Q7S-Pad9)") (class "Default")
      (node (ref "U6") (pin "9") (pinfunction "Q7S_9") (pintype "bidirectional"))
    )
  )
)
